# ai_breakout_mics5524_panel.net
KiCad netlist of a schematic drawn in EAGLE
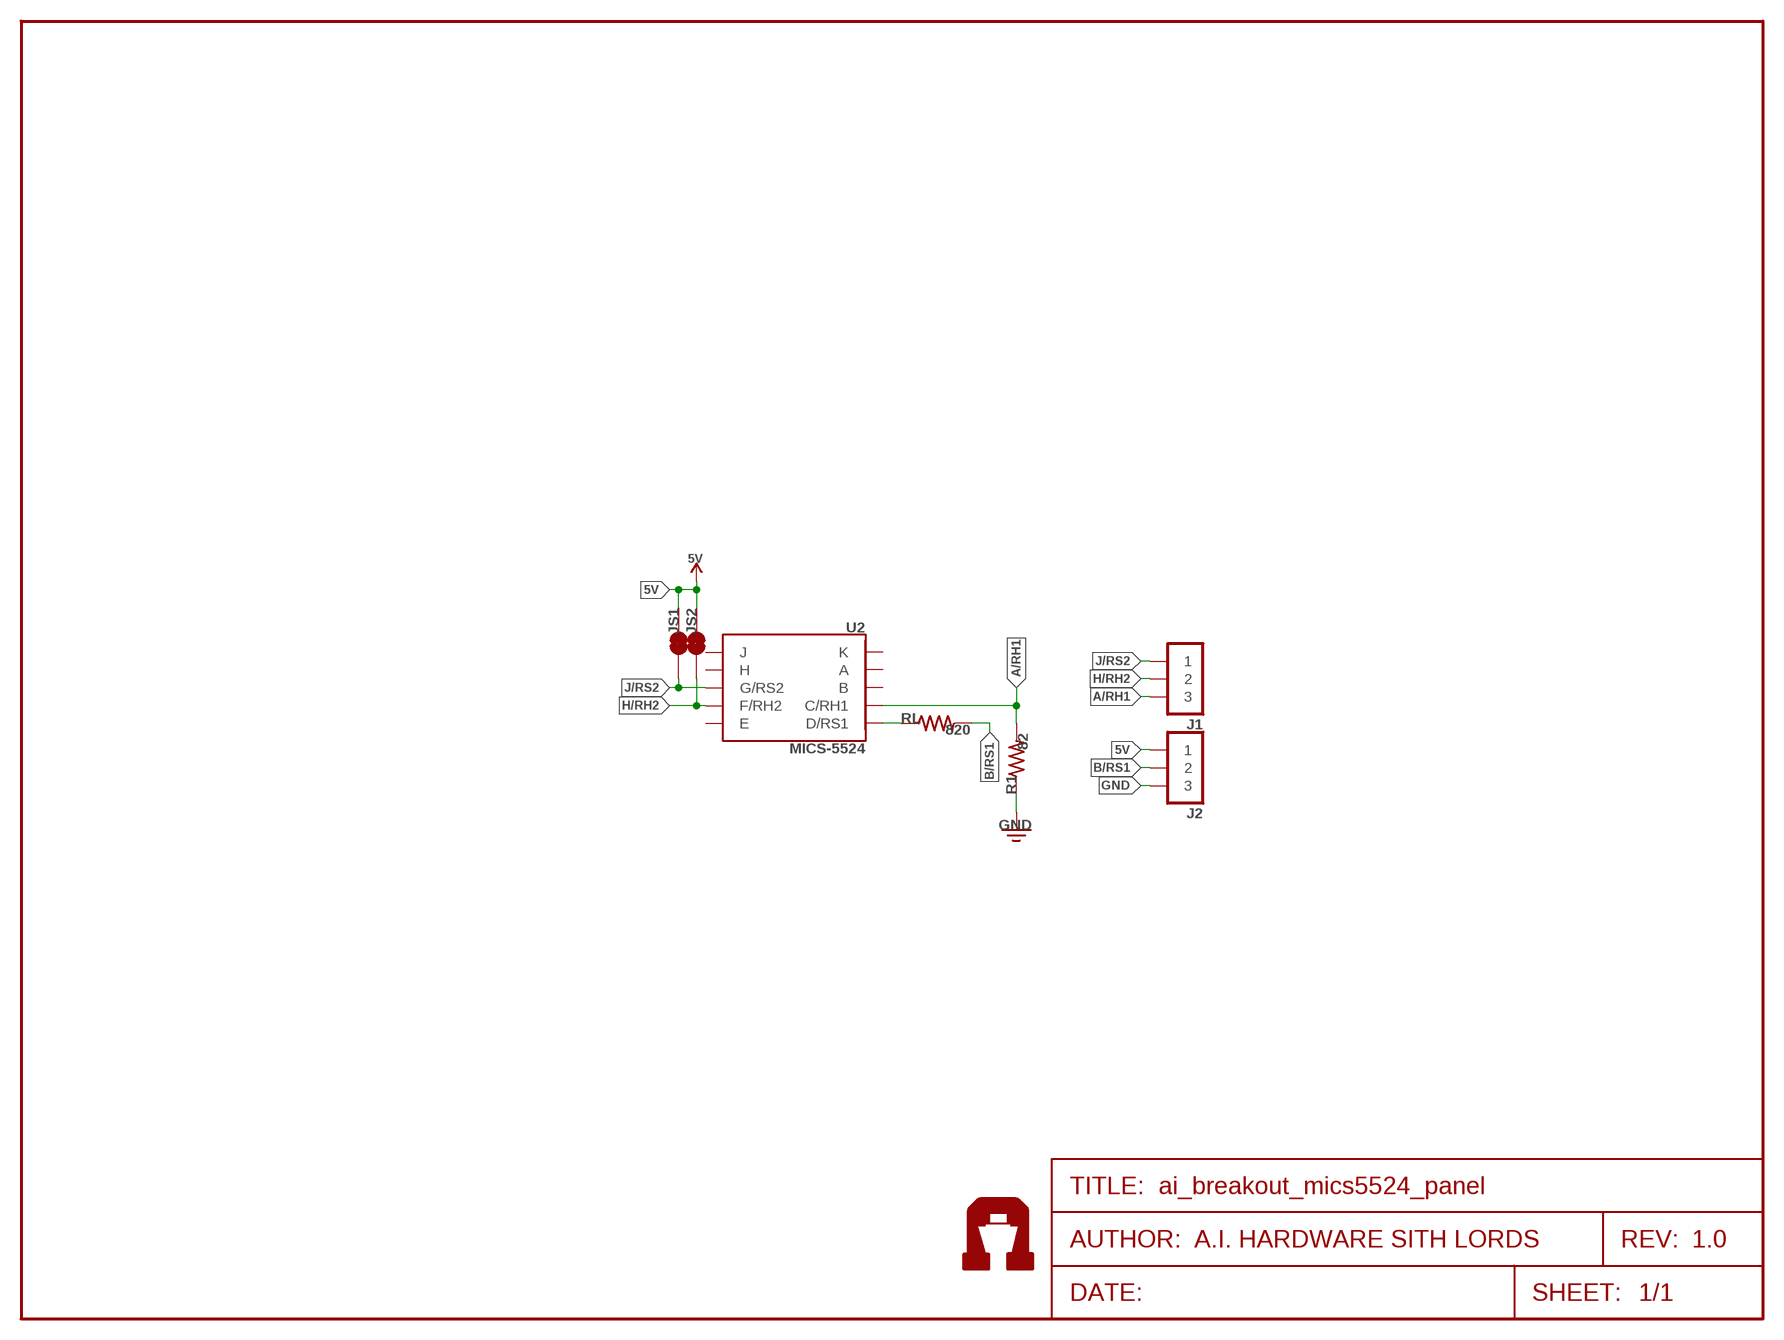
[diagram p0: schematic, sheet 1]

(export (version "E")
  (design (tool "Eeschema 10.0.6"))
  (components
    (comp (ref "J1")
      (value "1X03NOFIRST")
      (footprint "eagle-import:1X03-NOFIRST")
      (libsource (lib "eagle-import") (part "1X03NOFIRST"))
    )
    (comp (ref "J2")
      (value "1X03NOFIRST")
      (footprint "eagle-import:1X03-NOFIRST")
      (libsource (lib "eagle-import") (part "1X03NOFIRST"))
    )
    (comp (ref "JS1")
      (value "1X02-SJ-NCT")
      (footprint "eagle-import:1X02-SJ-NCT")
      (libsource (lib "eagle-import") (part "1X02-SJ-NCT"))
    )
    (comp (ref "JS2")
      (value "1X02-SJ-NCT")
      (footprint "eagle-import:1X02-SJ-NCT")
      (libsource (lib "eagle-import") (part "1X02-SJ-NCT"))
    )
    (comp (ref "R1")
      (value "82")
      (footprint "eagle-import:RES-0603")
      (libsource (lib "eagle-import") (part "RES0603"))
    )
    (comp (ref "RL")
      (value "820")
      (footprint "eagle-import:RES-0603")
      (libsource (lib "eagle-import") (part "RES0603"))
    )
    (comp (ref "U$3")
      (value "AI-LOGOXS")
      (footprint "eagle-import:AI-LOGO-XS")
      (libsource (lib "eagle-import") (part "AI-LOGOXS"))
    )
    (comp (ref "U2")
      (value "MICS-5524")
      (footprint "eagle-import:MICS-SMD10")
      (libsource (lib "eagle-import") (part "MICS-5524"))
    )
  )
  (nets
    (net (code "1") (name "5V") (class "Default")
      (node (ref "J2") (pin "1") (pinfunction "1_1") (pintype "bidirectional"))
      (node (ref "JS1") (pin "2") (pinfunction "2_2") (pintype "passive"))
      (node (ref "JS2") (pin "2") (pinfunction "2_2") (pintype "passive"))
    )
    (net (code "2") (name "A{slash}RH1") (class "Default")
      (node (ref "J1") (pin "3") (pinfunction "3_3") (pintype "bidirectional"))
      (node (ref "R1") (pin "2") (pinfunction "2_2") (pintype "passive"))
      (node (ref "U2") (pin "C") (pinfunction "C/RH1_C") (pintype "bidirectional"))
    )
    (net (code "3") (name "B{slash}RS1") (class "Default")
      (node (ref "J2") (pin "2") (pinfunction "2_2") (pintype "bidirectional"))
      (node (ref "RL") (pin "2") (pinfunction "2_2") (pintype "passive"))
    )
    (net (code "4") (name "GND") (class "Default")
      (node (ref "J2") (pin "3") (pinfunction "3_3") (pintype "bidirectional"))
      (node (ref "R1") (pin "1") (pinfunction "1_1") (pintype "passive"))
    )
    (net (code "5") (name "H{slash}RH2") (class "Default")
      (node (ref "J1") (pin "2") (pinfunction "2_2") (pintype "bidirectional"))
      (node (ref "JS2") (pin "1") (pinfunction "1_1") (pintype "passive"))
      (node (ref "U2") (pin "F") (pinfunction "F/RH2_F") (pintype "bidirectional"))
    )
    (net (code "6") (name "J{slash}RS2") (class "Default")
      (node (ref "J1") (pin "1") (pinfunction "1_1") (pintype "bidirectional"))
      (node (ref "JS1") (pin "1") (pinfunction "1_1") (pintype "passive"))
      (node (ref "U2") (pin "G") (pinfunction "G/RS2_G") (pintype "bidirectional"))
    )
    (net (code "7") (name "Net-(U2-D{slash}RS1)") (class "Default")
      (node (ref "RL") (pin "1") (pinfunction "1_1") (pintype "passive"))
      (node (ref "U2") (pin "D") (pinfunction "D/RS1_D") (pintype "bidirectional"))
    )
    (net (code "8") (name "unconnected-(U2-PadA)") (class "Default")
      (node (ref "U2") (pin "A") (pinfunction "A_A") (pintype "bidirectional"))
    )
    (net (code "9") (name "unconnected-(U2-PadB)") (class "Default")
      (node (ref "U2") (pin "B") (pinfunction "B_B") (pintype "bidirectional"))
    )
    (net (code "10") (name "unconnected-(U2-PadE)") (class "Default")
      (node (ref "U2") (pin "E") (pinfunction "E_E") (pintype "bidirectional"))
    )
    (net (code "11") (name "unconnected-(U2-PadH)") (class "Default")
      (node (ref "U2") (pin "H") (pinfunction "H_H") (pintype "bidirectional"))
    )
    (net (code "12") (name "unconnected-(U2-PadJ)") (class "Default")
      (node (ref "U2") (pin "J") (pinfunction "J_J") (pintype "bidirectional"))
    )
    (net (code "13") (name "unconnected-(U2-PadK)") (class "Default")
      (node (ref "U2") (pin "K") (pinfunction "K_K") (pintype "bidirectional"))
    )
  )
)
